# Silent_Stepper_Driver_Y_Z_E_Axis.net
KiCad netlist of a schematic drawn in EAGLE
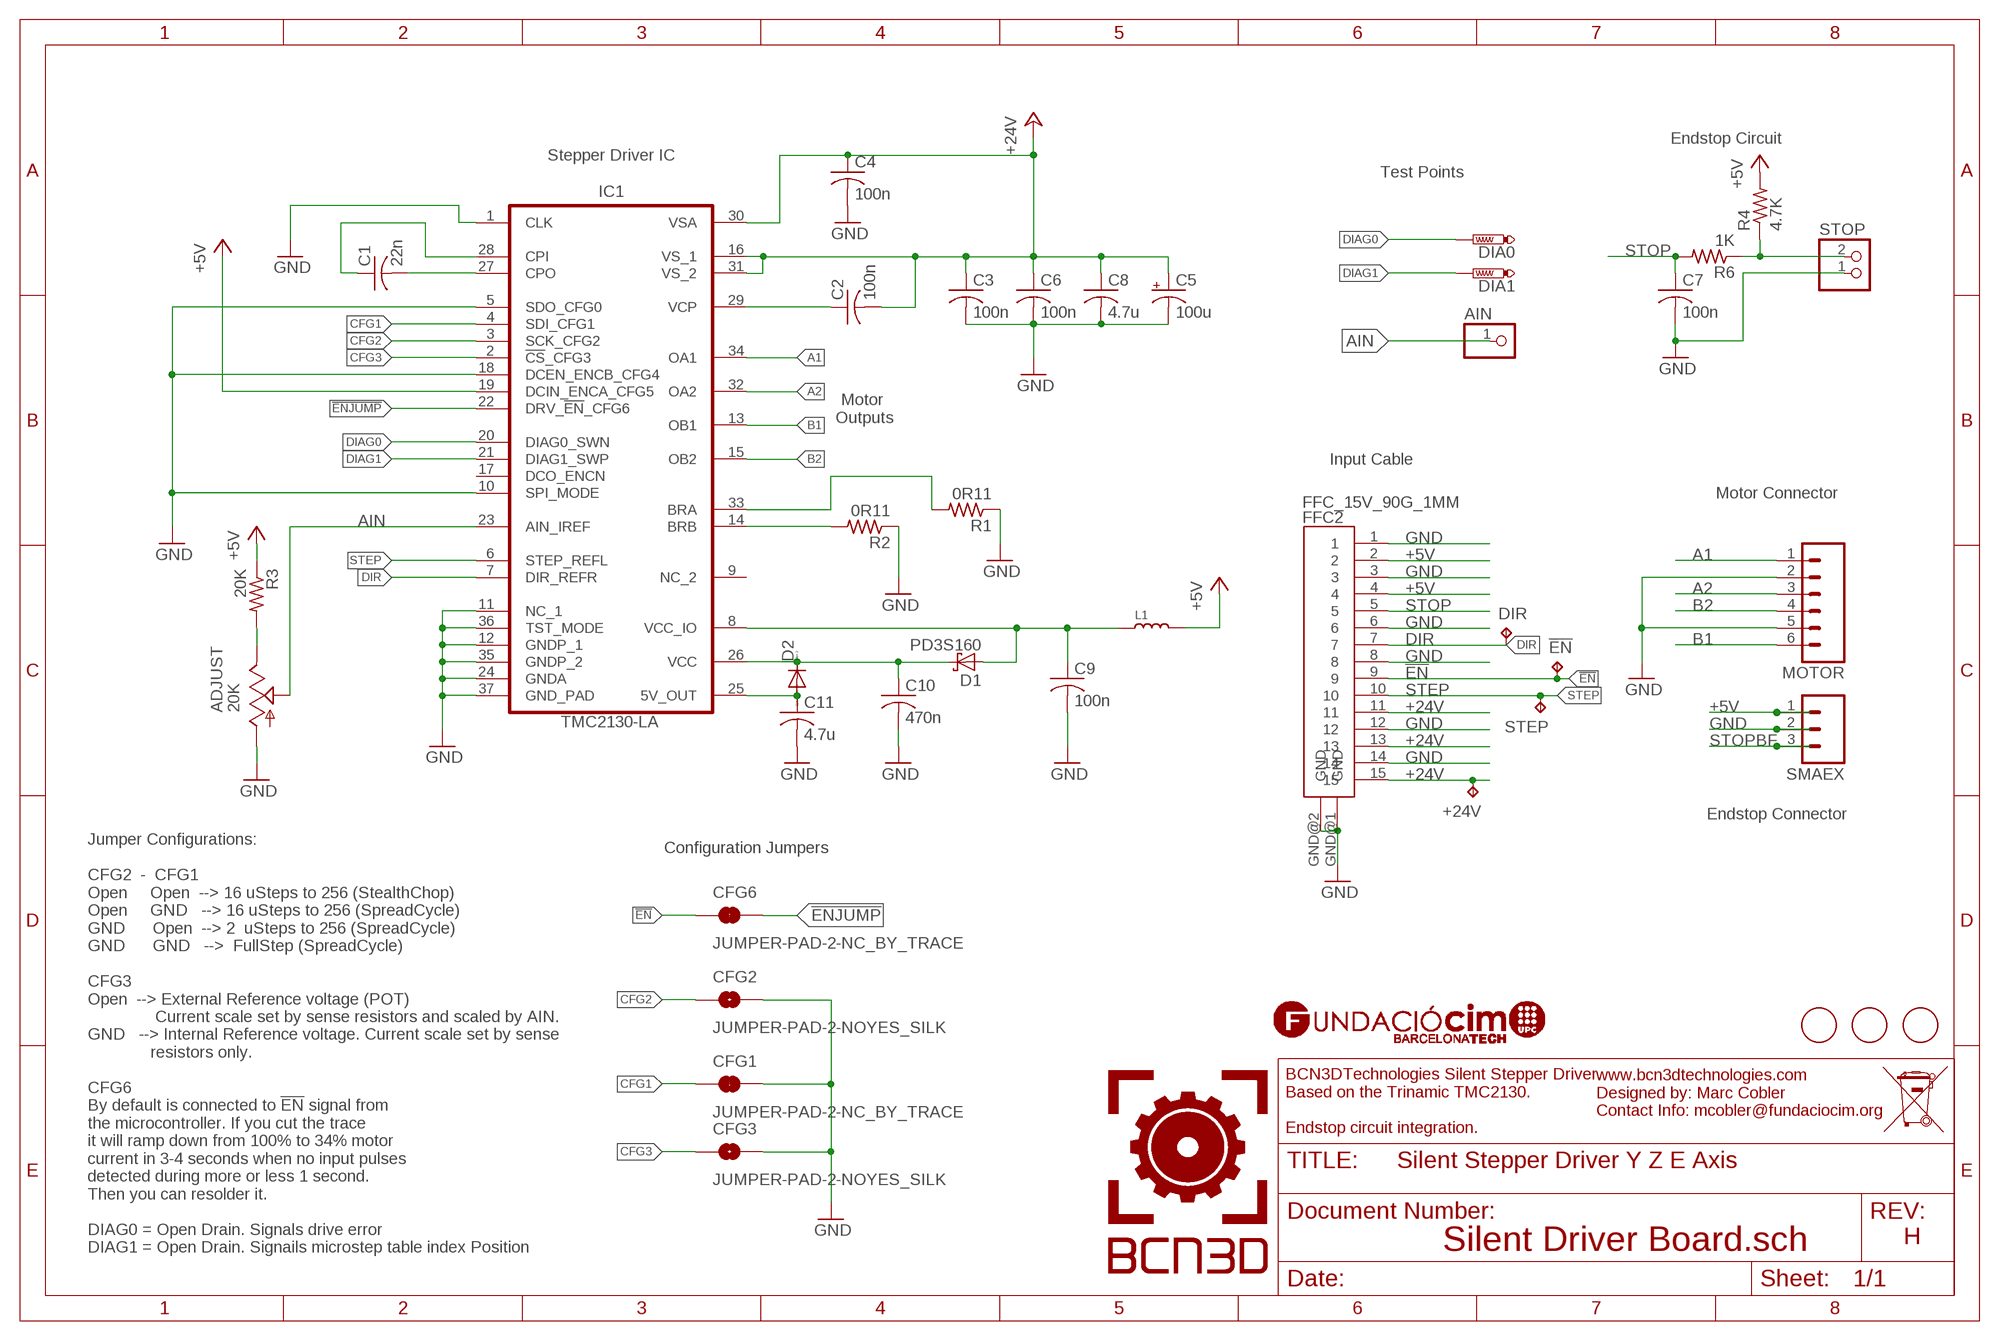
[diagram p0: schematic, sheet 1]

(export (version "E")
  (design (tool "Eeschema 10.0.6"))
  (components
    (comp (ref "!EN")
      (value "TPB1,27")
      (footprint "eagle-import:B1,27")
      (libsource (lib "eagle-import") (part "TPB1,27"))
    )
    (comp (ref "+24V")
      (value "TPB1,27")
      (footprint "eagle-import:B1,27")
      (libsource (lib "eagle-import") (part "TPB1,27"))
    )
    (comp (ref "ADJUST")
      (value "20K")
      (footprint "eagle-import:3223G")
      (fields (field (name "MF") "BOURNS") (field (name "MPN") "3314G-2-203E"))
      (libsource (lib "eagle-import") (part "TRIM_US-3223G"))
    )
    (comp (ref "AIN")
      (value "PINHD-1X1")
      (footprint "eagle-import:1X01")
      (libsource (lib "eagle-import") (part "PINHD-1X1"))
    )
    (comp (ref "C1")
      (value "22n")
      (footprint "eagle-import:C0603K")
      (fields (field (name "MF") "MURATA") (field (name "MPN") "GCM188R72A223KA37D"))
      (libsource (lib "eagle-import") (part "C-USC0603K"))
    )
    (comp (ref "C2")
      (value "100n")
      (footprint "eagle-import:C0603K")
      (fields (field (name "MF") "AVX") (field (name "MPN") "06035C104KAT2A"))
      (libsource (lib "eagle-import") (part "C-USC0603K"))
    )
    (comp (ref "C3")
      (value "100n")
      (footprint "eagle-import:C0603K")
      (fields (field (name "MF") "AVX") (field (name "MPN") "06035C104KAT2A"))
      (libsource (lib "eagle-import") (part "C-USC0603K"))
    )
    (comp (ref "C4")
      (value "100n")
      (footprint "eagle-import:C0603K")
      (fields (field (name "MF") "AVX") (field (name "MPN") "06035C104KAT2A"))
      (libsource (lib "eagle-import") (part "C-USC0603K"))
    )
    (comp (ref "C5")
      (value "100u")
      (footprint "eagle-import:UD-6,3X7,7_NICHICON")
      (fields (field (name "MF") "PANASONIC ELECTRONIC COMPONENTS") (field (name "MPN") "EEE1HA101UAP"))
      (libsource (lib "eagle-import") (part "CPOL-USUD-6,3X7,7"))
    )
    (comp (ref "C6")
      (value "100n")
      (footprint "eagle-import:C0603K")
      (fields (field (name "MF") "AVX") (field (name "MPN") "06035C104KAT2A"))
      (libsource (lib "eagle-import") (part "C-USC0603K"))
    )
    (comp (ref "C7")
      (value "100n")
      (footprint "eagle-import:C0603K")
      (fields (field (name "MF") "AVX") (field (name "MPN") "06035C104KAT2A"))
      (libsource (lib "eagle-import") (part "C-USC0603K"))
    )
    (comp (ref "C8")
      (value "4.7u")
      (footprint "eagle-import:C1210")
      (fields (field (name "MF") "KEMET") (field (name "MPN") "C1210X475K5RACTU"))
      (libsource (lib "eagle-import") (part "C-USC1210"))
    )
    (comp (ref "C9")
      (value "100n")
      (footprint "eagle-import:C0603K")
      (fields (field (name "MF") "AVX") (field (name "MPN") "06035C104KAT2A"))
      (libsource (lib "eagle-import") (part "C-USC0603K"))
    )
    (comp (ref "C10")
      (value "470n")
      (footprint "eagle-import:C0603K")
      (fields (field (name "MF") "MURATA") (field (name "MPN") "GRM188R71C474KA88D"))
      (libsource (lib "eagle-import") (part "C-USC0603K"))
    )
    (comp (ref "C11")
      (value "4.7u")
      (footprint "eagle-import:C0805")
      (fields (field (name "MF") "AVX") (field (name "MPN") "0805YC475KAT2A"))
      (libsource (lib "eagle-import") (part "C-USC0805"))
    )
    (comp (ref "CFG1")
      (value "JUMPER-PAD-2-NC_BY_TRACE")
      (footprint "eagle-import:PAD-JUMPER-2-NC_BY_TRACE_YES_SILK")
      (libsource (lib "eagle-import") (part "JUMPER-PAD-2-NC_BY_TRACE"))
    )
    (comp (ref "CFG2")
      (value "JUMPER-PAD-2-NOYES_SILK")
      (footprint "eagle-import:PAD-JUMPER-2-NO_YES_SILK")
      (libsource (lib "eagle-import") (part "JUMPER-PAD-2-NOYES_SILK"))
    )
    (comp (ref "CFG3")
      (value "JUMPER-PAD-2-NOYES_SILK")
      (footprint "eagle-import:PAD-JUMPER-2-NO_YES_SILK")
      (libsource (lib "eagle-import") (part "JUMPER-PAD-2-NOYES_SILK"))
    )
    (comp (ref "CFG6")
      (value "JUMPER-PAD-2-NC_BY_TRACE")
      (footprint "eagle-import:PAD-JUMPER-2-NC_BY_TRACE_YES_SILK")
      (libsource (lib "eagle-import") (part "JUMPER-PAD-2-NC_BY_TRACE"))
    )
    (comp (ref "D1")
      (value "PD3S160")
      (footprint "eagle-import:POWERDI323")
      (fields (field (name "MF") "DIODES INC.") (field (name "MPN") "PD3S160-7"))
      (libsource (lib "eagle-import") (part "PD3S160"))
    )
    (comp (ref "D2")
      (value "DIODE-MINIMELF")
      (footprint "eagle-import:MINIMELF")
      (fields (field (name "MF") "NXP") (field (name "MPN") "PMLL4448"))
      (libsource (lib "eagle-import") (part "DIODE-MINIMELF"))
    )
    (comp (ref "DIA0")
      (value "PTR1TP12R")
      (footprint "eagle-import:TP12R")
      (libsource (lib "eagle-import") (part "PTR1TP12R"))
    )
    (comp (ref "DIA1")
      (value "PTR1TP12R")
      (footprint "eagle-import:TP12R")
      (libsource (lib "eagle-import") (part "PTR1TP12R"))
    )
    (comp (ref "DIR")
      (value "TPB1,27")
      (footprint "eagle-import:B1,27")
      (libsource (lib "eagle-import") (part "TPB1,27"))
    )
    (comp (ref "FFC2")
      (value "FFC_15V_90G_1MM")
      (footprint "eagle-import:TE_FFC_CON1MM")
      (libsource (lib "eagle-import") (part "FFC_15V_90G_1MM"))
    )
    (comp (ref "IC1")
      (value "TMC2130-LA")
      (footprint "eagle-import:TMC_QFN36_0.5_5.0X6.0")
      (fields (field (name "MANUFACTURER") " TRINAMIC "))
      (libsource (lib "eagle-import") (part "TMC2130-LA"))
    )
    (comp (ref "L1")
      (value "INDUCTOR/FERRITE-BEAD'0603'")
      (footprint "eagle-import:L0603")
      (fields (field (name "MF") "BOURNS") (field (name "MPN") "CRL0603-FW-R470ELF"))
      (libsource (lib "eagle-import") (part "INDUCTOR/FERRITE-BEAD'0603'"))
    )
    (comp (ref "MOTOR")
      (value "M06")
      (footprint "eagle-import:JST-6-PTH")
      (fields
        (field (name "MF") "JST (JAPAN SOLDERLESS TERMINALS)")
        (field (name "MPN") "S6B-PH-K-S (LF)(SN)")
      )
      (libsource (lib "eagle-import") (part "M06"))
    )
    (comp (ref "R1")
      (value "0R11")
      (footprint "eagle-import:R0805")
      (fields (field (name "MF") "PANASONIC ELECTRONIC COMPONENTS") (field (name "MPN") "ERJ6BSFR11V"))
      (libsource (lib "eagle-import") (part "R-US_R0805"))
    )
    (comp (ref "R2")
      (value "0R11")
      (footprint "eagle-import:R0805")
      (fields (field (name "MF") "PANASONIC ELECTRONIC COMPONENTS") (field (name "MPN") "ERJ6BSFR11V"))
      (libsource (lib "eagle-import") (part "R-US_R0805"))
    )
    (comp (ref "R3")
      (value "20K")
      (footprint "eagle-import:R0603")
      (fields (field (name "MF") "MULTICOMP") (field (name "MPN") "MC0201L6F2002SE."))
      (libsource (lib "eagle-import") (part "R-US_R0603"))
    )
    (comp (ref "R4")
      (value "4.7K")
      (footprint "eagle-import:R0603")
      (fields (field (name "MF") "PANASONIC ELECTRONIC COMPONENTS") (field (name "MPN") "ERJP06F4701V"))
      (libsource (lib "eagle-import") (part "R-US_R0603"))
    )
    (comp (ref "R6")
      (value "1K")
      (footprint "eagle-import:R0603")
      (fields (field (name "MF") "BOURNS") (field (name "MPN") "CR0805-JW-102ELF"))
      (libsource (lib "eagle-import") (part "R-US_R0603"))
    )
    (comp (ref "SMAEX")
      (value "M03PTH")
      (footprint "eagle-import:1X03")
      (libsource (lib "eagle-import") (part "M03PTH"))
    )
    (comp (ref "STEP")
      (value "TPB1,27")
      (footprint "eagle-import:B1,27")
      (libsource (lib "eagle-import") (part "TPB1,27"))
    )
    (comp (ref "STOP")
      (value "JST_2PIN-THM-RA")
      (footprint "eagle-import:JST-PH-2-THM-RA")
      (fields
        (field (name "MF") "JST (JAPAN SOLDERLESS TERMINALS)")
        (field (name "MPN") "S2B-PH-K-S (LF)(SN)")
      )
      (libsource (lib "eagle-import") (part "JST_2PIN-THM-RA"))
    )
    (comp (ref "U$2")
      (value "FIDUCIAL")
      (footprint "eagle-import:FIDUCIAL_1MM")
      (libsource (lib "eagle-import") (part "FIDUCIAL"))
    )
    (comp (ref "U$3")
      (value "FIDUCIAL")
      (footprint "eagle-import:FIDUCIAL_1MM")
      (libsource (lib "eagle-import") (part "FIDUCIAL"))
    )
    (comp (ref "U$4")
      (value "FIDUCIAL")
      (footprint "eagle-import:FIDUCIAL_1MM")
      (libsource (lib "eagle-import") (part "FIDUCIAL"))
    )
  )
  (nets
    (net (code "1") (name "+5V") (class "Default")
      (node (ref "FFC2") (pin "2") (pinfunction "2_2") (pintype "bidirectional"))
      (node (ref "FFC2") (pin "4") (pinfunction "4_4") (pintype "bidirectional"))
      (node (ref "IC1") (pin "19") (pinfunction "DCIN_ENCA_CFG5_19") (pintype "input"))
      (node (ref "L1") (pin "2") (pinfunction "2_2") (pintype "passive"))
      (node (ref "R3") (pin "1") (pinfunction "1_1") (pintype "passive"))
      (node (ref "R4") (pin "2") (pinfunction "2_2") (pintype "passive"))
      (node (ref "SMAEX") (pin "1") (pinfunction "1_1") (pintype "passive"))
    )
    (net (code "2") (name "+24V") (class "Default")
      (node (ref "+24V") (pin "TP") (pinfunction "TP_TP") (pintype "input"))
      (node (ref "C2") (pin "2") (pinfunction "2_2") (pintype "passive"))
      (node (ref "C3") (pin "1") (pinfunction "1_1") (pintype "passive"))
      (node (ref "C4") (pin "1") (pinfunction "1_1") (pintype "passive"))
      (node (ref "C5") (pin "+") (pinfunction "+_+") (pintype "passive"))
      (node (ref "C6") (pin "1") (pinfunction "1_1") (pintype "passive"))
      (node (ref "C8") (pin "1") (pinfunction "1_1") (pintype "passive"))
      (node (ref "FFC2") (pin "11") (pinfunction "11_11") (pintype "bidirectional"))
      (node (ref "FFC2") (pin "13") (pinfunction "13_13") (pintype "bidirectional"))
      (node (ref "FFC2") (pin "15") (pinfunction "15_15") (pintype "bidirectional"))
      (node (ref "IC1") (pin "16") (pinfunction "VS_1_16") (pintype "power_in"))
      (node (ref "IC1") (pin "30") (pinfunction "VSA_30") (pintype "power_in"))
      (node (ref "IC1") (pin "31") (pinfunction "VS_2_31") (pintype "power_in"))
    )
    (net (code "3") (name "/STOP") (class "Default")
      (node (ref "C7") (pin "1") (pinfunction "1_1") (pintype "passive"))
      (node (ref "FFC2") (pin "5") (pinfunction "5_5") (pintype "bidirectional"))
      (node (ref "R6") (pin "2") (pinfunction "2_2") (pintype "passive"))
    )
    (net (code "4") (name "/STOPBF") (class "Default")
      (node (ref "R4") (pin "1") (pinfunction "1_1") (pintype "passive"))
      (node (ref "R6") (pin "1") (pinfunction "1_1") (pintype "passive"))
      (node (ref "SMAEX") (pin "3") (pinfunction "3_3") (pintype "passive"))
      (node (ref "STOP") (pin "2") (pinfunction "1_2") (pintype "passive"))
    )
    (net (code "5") (name "/~{ENJUMP}") (class "Default")
      (node (ref "CFG6") (pin "2") (pinfunction "2_2") (pintype "passive"))
      (node (ref "IC1") (pin "22") (pinfunction "DRV_~{EN}_CFG6_22") (pintype "input"))
    )
    (net (code "6") (name "/~{EN}") (class "Default")
      (node (ref "!EN") (pin "TP") (pinfunction "TP_TP") (pintype "input"))
      (node (ref "CFG6") (pin "1") (pinfunction "1_1") (pintype "passive"))
      (node (ref "FFC2") (pin "9") (pinfunction "9_9") (pintype "bidirectional"))
    )
    (net (code "7") (name "A1") (class "Default")
      (node (ref "IC1") (pin "34") (pinfunction "OA1_34") (pintype "output"))
      (node (ref "MOTOR") (pin "1") (pinfunction "1_1") (pintype "passive"))
    )
    (net (code "8") (name "A2") (class "Default")
      (node (ref "IC1") (pin "32") (pinfunction "OA2_32") (pintype "output"))
      (node (ref "MOTOR") (pin "3") (pinfunction "3_3") (pintype "passive"))
    )
    (net (code "9") (name "AIN") (class "Default")
      (node (ref "ADJUST") (pin "2") (pinfunction "S_2") (pintype "passive"))
      (node (ref "AIN") (pin "1") (pinfunction "1_1") (pintype "passive"))
      (node (ref "IC1") (pin "23") (pinfunction "AIN_IREF_23") (pintype "input"))
    )
    (net (code "10") (name "B1") (class "Default")
      (node (ref "IC1") (pin "13") (pinfunction "OB1_13") (pintype "output"))
      (node (ref "MOTOR") (pin "6") (pinfunction "6_6") (pintype "passive"))
    )
    (net (code "11") (name "B2") (class "Default")
      (node (ref "IC1") (pin "15") (pinfunction "OB2_15") (pintype "output"))
      (node (ref "MOTOR") (pin "4") (pinfunction "4_4") (pintype "passive"))
    )
    (net (code "12") (name "CFG1") (class "Default")
      (node (ref "CFG1") (pin "1") (pinfunction "1_1") (pintype "passive"))
      (node (ref "IC1") (pin "4") (pinfunction "SDI_CFG1_4") (pintype "input"))
    )
    (net (code "13") (name "CFG2") (class "Default")
      (node (ref "CFG2") (pin "1") (pinfunction "1_1") (pintype "passive"))
      (node (ref "IC1") (pin "3") (pinfunction "SCK_CFG2_3") (pintype "input"))
    )
    (net (code "14") (name "CFG3") (class "Default")
      (node (ref "CFG3") (pin "1") (pinfunction "1_1") (pintype "passive"))
      (node (ref "IC1") (pin "2") (pinfunction "~{CS}_CFG3_2") (pintype "input"))
    )
    (net (code "15") (name "DIAG0") (class "Default")
      (node (ref "DIA0") (pin "TP") (pinfunction "TP_TP") (pintype "input"))
      (node (ref "IC1") (pin "20") (pinfunction "DIAG0_SWN_20") (pintype "bidirectional"))
    )
    (net (code "16") (name "DIAG1") (class "Default")
      (node (ref "DIA1") (pin "TP") (pinfunction "TP_TP") (pintype "input"))
      (node (ref "IC1") (pin "21") (pinfunction "DIAG1_SWP_21") (pintype "bidirectional"))
    )
    (net (code "17") (name "DIR") (class "Default")
      (node (ref "DIR") (pin "TP") (pinfunction "TP_TP") (pintype "input"))
      (node (ref "FFC2") (pin "7") (pinfunction "7_7") (pintype "bidirectional"))
      (node (ref "IC1") (pin "7") (pinfunction "DIR_REFR_7") (pintype "input"))
    )
    (net (code "18") (name "GND") (class "Default")
      (node (ref "ADJUST") (pin "1") (pinfunction "A_1") (pintype "passive"))
      (node (ref "C10") (pin "2") (pinfunction "2_2") (pintype "passive"))
      (node (ref "C11") (pin "2") (pinfunction "2_2") (pintype "passive"))
      (node (ref "C3") (pin "2") (pinfunction "2_2") (pintype "passive"))
      (node (ref "C4") (pin "2") (pinfunction "2_2") (pintype "passive"))
      (node (ref "C5") (pin "-") (pinfunction "-_-") (pintype "passive"))
      (node (ref "C6") (pin "2") (pinfunction "2_2") (pintype "passive"))
      (node (ref "C7") (pin "2") (pinfunction "2_2") (pintype "passive"))
      (node (ref "C8") (pin "2") (pinfunction "2_2") (pintype "passive"))
      (node (ref "C9") (pin "2") (pinfunction "2_2") (pintype "passive"))
      (node (ref "CFG1") (pin "2") (pinfunction "2_2") (pintype "passive"))
      (node (ref "CFG2") (pin "2") (pinfunction "2_2") (pintype "passive"))
      (node (ref "CFG3") (pin "2") (pinfunction "2_2") (pintype "passive"))
      (node (ref "FFC2") (pin "1") (pinfunction "1_1") (pintype "bidirectional"))
      (node (ref "FFC2") (pin "12") (pinfunction "12_12") (pintype "bidirectional"))
      (node (ref "FFC2") (pin "14") (pinfunction "14_14") (pintype "bidirectional"))
      (node (ref "FFC2") (pin "3") (pinfunction "3_3") (pintype "bidirectional"))
      (node (ref "FFC2") (pin "6") (pinfunction "6_6") (pintype "bidirectional"))
      (node (ref "FFC2") (pin "8") (pinfunction "8_8") (pintype "bidirectional"))
      (node (ref "FFC2") (pin "GND@1") (pinfunction "GND_GND@1") (pintype "bidirectional"))
      (node (ref "FFC2") (pin "GND@2") (pinfunction "GND_GND@2") (pintype "bidirectional"))
      (node (ref "IC1") (pin "1") (pinfunction "CLK_1") (pintype "input"))
      (node (ref "IC1") (pin "10") (pinfunction "SPI_MODE_10") (pintype "input"))
      (node (ref "IC1") (pin "11") (pinfunction "NC_1_11") (pintype "power_in"))
      (node (ref "IC1") (pin "12") (pinfunction "GNDP_1_12") (pintype "power_in"))
      (node (ref "IC1") (pin "18") (pinfunction "DCEN_ENCB_CFG4_18") (pintype "input"))
      (node (ref "IC1") (pin "24") (pinfunction "GNDA_24") (pintype "power_in"))
      (node (ref "IC1") (pin "35") (pinfunction "GNDP_2_35") (pintype "power_in"))
      (node (ref "IC1") (pin "36") (pinfunction "TST_MODE_36") (pintype "input"))
      (node (ref "IC1") (pin "37") (pinfunction "GND_PAD_37") (pintype "power_in"))
      (node (ref "IC1") (pin "5") (pinfunction "SDO_CFG0_5") (pintype "bidirectional"))
      (node (ref "MOTOR") (pin "2") (pinfunction "2_2") (pintype "passive"))
      (node (ref "MOTOR") (pin "5") (pinfunction "5_5") (pintype "passive"))
      (node (ref "R1") (pin "1") (pinfunction "1_1") (pintype "passive"))
      (node (ref "R2") (pin "1") (pinfunction "1_1") (pintype "passive"))
      (node (ref "SMAEX") (pin "2") (pinfunction "2_2") (pintype "passive"))
      (node (ref "STOP") (pin "1") (pinfunction "2_1") (pintype "passive"))
    )
    (net (code "19") (name "Net-(ADJUST-E)") (class "Default")
      (node (ref "ADJUST") (pin "3") (pinfunction "E_3") (pintype "passive"))
      (node (ref "R3") (pin "2") (pinfunction "2_2") (pintype "passive"))
    )
    (net (code "20") (name "Net-(IC1-5V_OUT)") (class "Default")
      (node (ref "C11") (pin "1") (pinfunction "1_1") (pintype "passive"))
      (node (ref "D2") (pin "A") (pinfunction "A_A") (pintype "passive"))
      (node (ref "IC1") (pin "25") (pinfunction "5V_OUT_25") (pintype "power_in"))
    )
    (net (code "21") (name "Net-(IC1-BRA)") (class "Default")
      (node (ref "IC1") (pin "33") (pinfunction "BRA_33") (pintype "output"))
      (node (ref "R1") (pin "2") (pinfunction "2_2") (pintype "passive"))
    )
    (net (code "22") (name "Net-(IC1-BRB)") (class "Default")
      (node (ref "IC1") (pin "14") (pinfunction "BRB_14") (pintype "output"))
      (node (ref "R2") (pin "2") (pinfunction "2_2") (pintype "passive"))
    )
    (net (code "23") (name "Net-(IC1-CPI)") (class "Default")
      (node (ref "C1") (pin "1") (pinfunction "1_1") (pintype "passive"))
      (node (ref "IC1") (pin "28") (pinfunction "CPI_28") (pintype "input"))
    )
    (net (code "24") (name "Net-(IC1-CPO)") (class "Default")
      (node (ref "C1") (pin "2") (pinfunction "2_2") (pintype "passive"))
      (node (ref "IC1") (pin "27") (pinfunction "CPO_27") (pintype "output"))
    )
    (net (code "25") (name "Net-(IC1-VCC)") (class "Default")
      (node (ref "C10") (pin "1") (pinfunction "1_1") (pintype "passive"))
      (node (ref "D1") (pin "C") (pinfunction "C_C") (pintype "passive"))
      (node (ref "D2") (pin "C") (pinfunction "C_C") (pintype "passive"))
      (node (ref "IC1") (pin "26") (pinfunction "VCC_26") (pintype "power_in"))
    )
    (net (code "26") (name "Net-(IC1-VCC_IO)") (class "Default")
      (node (ref "C9") (pin "1") (pinfunction "1_1") (pintype "passive"))
      (node (ref "D1") (pin "A") (pinfunction "A_A") (pintype "passive"))
      (node (ref "IC1") (pin "8") (pinfunction "VCC_IO_8") (pintype "power_in"))
      (node (ref "L1") (pin "1") (pinfunction "1_1") (pintype "passive"))
    )
    (net (code "27") (name "Net-(IC1-VCP)") (class "Default")
      (node (ref "C2") (pin "1") (pinfunction "1_1") (pintype "passive"))
      (node (ref "IC1") (pin "29") (pinfunction "VCP_29") (pintype "power_in"))
    )
    (net (code "28") (name "STEP") (class "Default")
      (node (ref "FFC2") (pin "10") (pinfunction "10_10") (pintype "bidirectional"))
      (node (ref "IC1") (pin "6") (pinfunction "STEP_REFL_6") (pintype "input"))
      (node (ref "STEP") (pin "TP") (pinfunction "TP_TP") (pintype "input"))
    )
    (net (code "29") (name "unconnected-(IC1-DCO_ENCN-Pad17)") (class "Default")
      (node (ref "IC1") (pin "17") (pinfunction "DCO_ENCN_17") (pintype "bidirectional"))
    )
    (net (code "30") (name "unconnected-(IC1-NC_2-Pad9)") (class "Default")
      (node (ref "IC1") (pin "9") (pinfunction "NC_2_9") (pintype "passive"))
    )
  )
)
